# power.net
KiCad netlist of a schematic drawn in Altium Designer
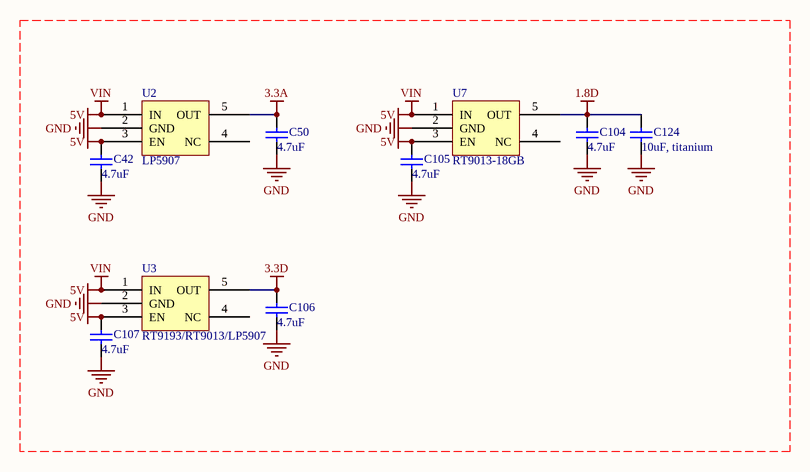
[diagram p0: power.SchDoc]

(export (version "E")
  (design (tool "Eeschema 10.0.6"))
  (components
    (comp (ref "C42")
      (value "4.7uF")
      (footprint "0603")
      (description "Capacitor")
      (fields (field (name "PUBLISHER") "Altium Limited"))
      (libsource (lib "RTC6705") (part "Cap"))
    )
    (comp (ref "C50")
      (value "4.7uF")
      (footprint "0603")
      (description "Capacitor")
      (fields (field (name "PUBLISHER") "Altium Limited"))
      (libsource (lib "RTC6705") (part "Cap"))
    )
    (comp (ref "C104")
      (value "4.7uF")
      (footprint "0603")
      (description "Capacitor")
      (fields (field (name "PUBLISHER") "Altium Limited"))
      (libsource (lib "RTC6705") (part "Cap"))
    )
    (comp (ref "C105")
      (value "4.7uF")
      (footprint "0603")
      (description "Capacitor")
      (fields (field (name "PUBLISHER") "Altium Limited"))
      (libsource (lib "RTC6705") (part "Cap"))
    )
    (comp (ref "C106")
      (value "4.7uF")
      (footprint "0603")
      (description "Capacitor")
      (fields (field (name "PUBLISHER") "Altium Limited"))
      (libsource (lib "RTC6705") (part "Cap"))
    )
    (comp (ref "C107")
      (value "4.7uF")
      (footprint "0603")
      (description "Capacitor")
      (fields (field (name "PUBLISHER") "Altium Limited"))
      (libsource (lib "RTC6705") (part "Cap"))
    )
    (comp (ref "C124")
      (value "10uF, titanium")
      (footprint "0805")
      (description "Capacitor")
      (fields (field (name "PUBLISHER") "Altium Limited"))
      (libsource (lib "RTC6705") (part "Cap"))
    )
    (comp (ref "U2") (value "LP5907") (footprint "SOT23-5") (libsource (lib "RTC6705") (part "LP5907")))
    (comp (ref "U3")
      (value "RT9193/RT9013/LP5907")
      (footprint "SOT23-5")
      (libsource (lib "RTC6705") (part "LP5907"))
    )
    (comp (ref "U7") (value "RT9013-18GB") (footprint "SOT23-5") (libsource (lib "RTC6705") (part "LP5907")))
  )
  (nets
    (net (code "1") (name "1.8D") (class "Default")
      (node (ref "C104") (pin "2") (pinfunction "2_2") (pintype "passive"))
      (node (ref "C124") (pin "2") (pinfunction "2_2") (pintype "passive"))
      (node (ref "U7") (pin "5") (pinfunction "OUT_5") (pintype "passive"))
    )
    (net (code "2") (name "3.3A") (class "Default")
      (node (ref "C50") (pin "2") (pinfunction "2_2") (pintype "passive"))
      (node (ref "U2") (pin "5") (pinfunction "OUT_5") (pintype "passive"))
    )
    (net (code "3") (name "3.3D") (class "Default")
      (node (ref "C106") (pin "2") (pinfunction "2_2") (pintype "passive"))
      (node (ref "U3") (pin "5") (pinfunction "OUT_5") (pintype "passive"))
    )
    (net (code "4") (name "5V") (class "Default")
      (node (ref "C105") (pin "2") (pinfunction "2_2") (pintype "passive"))
      (node (ref "C107") (pin "2") (pinfunction "2_2") (pintype "passive"))
      (node (ref "C42") (pin "2") (pinfunction "2_2") (pintype "passive"))
      (node (ref "U2") (pin "1") (pinfunction "IN_1") (pintype "passive"))
      (node (ref "U2") (pin "3") (pinfunction "EN_3") (pintype "passive"))
      (node (ref "U3") (pin "1") (pinfunction "IN_1") (pintype "passive"))
      (node (ref "U3") (pin "3") (pinfunction "EN_3") (pintype "passive"))
      (node (ref "U7") (pin "1") (pinfunction "IN_1") (pintype "passive"))
      (node (ref "U7") (pin "3") (pinfunction "EN_3") (pintype "passive"))
    )
    (net (code "5") (name "GND") (class "Default")
      (node (ref "C104") (pin "1") (pinfunction "1_1") (pintype "passive"))
      (node (ref "C105") (pin "1") (pinfunction "1_1") (pintype "passive"))
      (node (ref "C106") (pin "1") (pinfunction "1_1") (pintype "passive"))
      (node (ref "C107") (pin "1") (pinfunction "1_1") (pintype "passive"))
      (node (ref "C124") (pin "1") (pinfunction "1_1") (pintype "passive"))
      (node (ref "C42") (pin "1") (pinfunction "1_1") (pintype "passive"))
      (node (ref "C50") (pin "1") (pinfunction "1_1") (pintype "passive"))
      (node (ref "U2") (pin "2") (pinfunction "GND_2") (pintype "passive"))
      (node (ref "U3") (pin "2") (pinfunction "GND_2") (pintype "passive"))
      (node (ref "U7") (pin "2") (pinfunction "GND_2") (pintype "passive"))
    )
    (net (code "6") (name "unconnected-(U2-NC-Pad4)") (class "Default")
      (node (ref "U2") (pin "4") (pinfunction "NC_4") (pintype "passive"))
    )
    (net (code "7") (name "unconnected-(U3-NC-Pad4)") (class "Default")
      (node (ref "U3") (pin "4") (pinfunction "NC_4") (pintype "passive"))
    )
    (net (code "8") (name "unconnected-(U7-NC-Pad4)") (class "Default")
      (node (ref "U7") (pin "4") (pinfunction "NC_4") (pintype "passive"))
    )
  )
)
